# 7segement4digits1badidea-many-digits-mk-.net
KiCad netlist of a schematic drawn in EAGLE
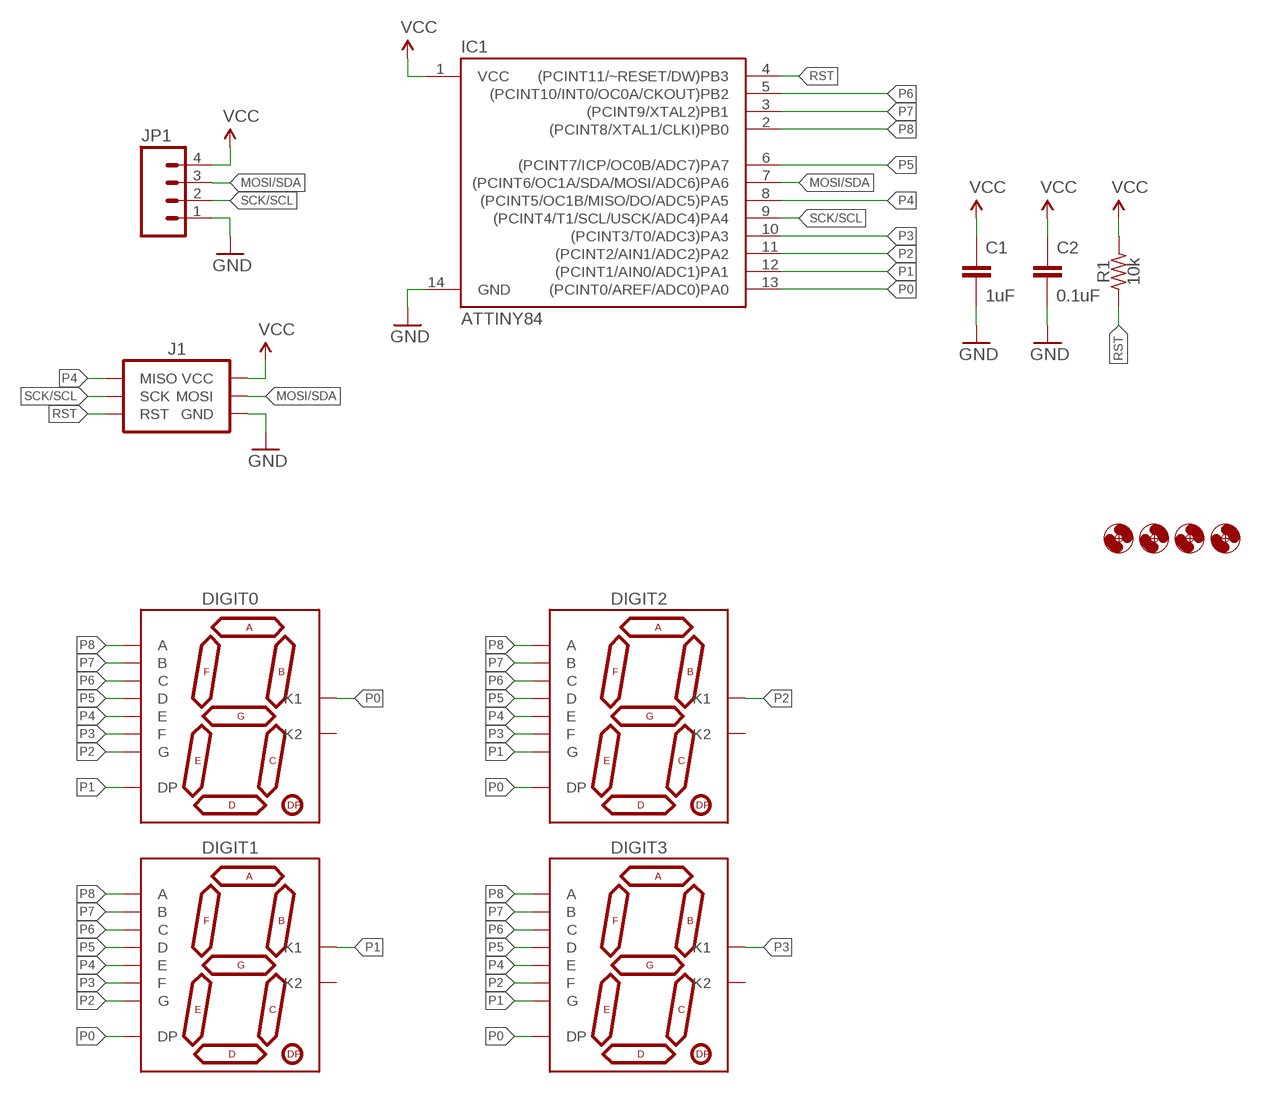
[diagram p0: schematic, sheet 1]

(export (version "E")
  (design (tool "Eeschema 10.0.6"))
  (components
    (comp (ref "C1")
      (value "1uF")
      (footprint "eagle-import:C0805")
      (libsource (lib "eagle-import") (part "CAPACITOR-CERAMICC0805"))
    )
    (comp (ref "C2")
      (value "0.1uF")
      (footprint "eagle-import:C0603")
      (libsource (lib "eagle-import") (part "CAPACITOR-CERAMICC0603"))
    )
    (comp (ref "DIGIT0")
      (value "7SEG_1DIGPTH-25.4MM")
      (footprint "eagle-import:7SEG_1DIG_25.4MM")
      (libsource (lib "eagle-import") (part "7SEG_1DIGPTH-25.4MM"))
    )
    (comp (ref "DIGIT1")
      (value "7SEG_1DIGPTH-25.4MM")
      (footprint "eagle-import:7SEG_1DIG_25.4MM")
      (libsource (lib "eagle-import") (part "7SEG_1DIGPTH-25.4MM"))
    )
    (comp (ref "DIGIT2")
      (value "7SEG_1DIGPTH-25.4MM")
      (footprint "eagle-import:7SEG_1DIG_25.4MM")
      (libsource (lib "eagle-import") (part "7SEG_1DIGPTH-25.4MM"))
    )
    (comp (ref "DIGIT3")
      (value "7SEG_1DIGPTH-25.4MM")
      (footprint "eagle-import:7SEG_1DIG_25.4MM")
      (libsource (lib "eagle-import") (part "7SEG_1DIGPTH-25.4MM"))
    )
    (comp (ref "H1")
      (value "HOLE#2")
      (footprint "eagle-import:HOLE-#2")
      (libsource (lib "eagle-import") (part "HOLE#2"))
    )
    (comp (ref "H2")
      (value "HOLE#2")
      (footprint "eagle-import:HOLE-#2")
      (libsource (lib "eagle-import") (part "HOLE#2"))
    )
    (comp (ref "H3")
      (value "HOLE#2")
      (footprint "eagle-import:HOLE-#2")
      (libsource (lib "eagle-import") (part "HOLE#2"))
    )
    (comp (ref "H4")
      (value "HOLE#2")
      (footprint "eagle-import:HOLE-#2")
      (libsource (lib "eagle-import") (part "HOLE#2"))
    )
    (comp (ref "IC1")
      (value "ATTINY84")
      (footprint "eagle-import:SO14")
      (libsource (lib "eagle-import") (part "ATTINY84"))
    )
    (comp (ref "J1")
      (value "AVR_SPI_PRG_6PTH")
      (footprint "eagle-import:2X3")
      (libsource (lib "eagle-import") (part "AVR_SPI_PRG_6PTH"))
    )
    (comp (ref "JP1")
      (value "M04PTH")
      (footprint "eagle-import:1X04-PTH-VERT")
      (libsource (lib "eagle-import") (part "M04PTH"))
    )
    (comp (ref "R1")
      (value "10k")
      (footprint "eagle-import:R0603")
      (libsource (lib "eagle-import") (part "RESISTORR0603"))
    )
  )
  (nets
    (net (code "1") (name "GND") (class "Default")
      (node (ref "C1") (pin "2") (pinfunction "2_2") (pintype "passive"))
      (node (ref "C2") (pin "2") (pinfunction "2_2") (pintype "passive"))
      (node (ref "IC1") (pin "14") (pinfunction "GND_14") (pintype "bidirectional"))
      (node (ref "J1") (pin "6") (pinfunction "GND_6") (pintype "passive"))
      (node (ref "JP1") (pin "1") (pinfunction "1_1") (pintype "passive"))
    )
    (net (code "2") (name "MOSI{slash}SDA") (class "Default")
      (node (ref "IC1") (pin "7") (pinfunction "(PCINT6/OC1A/SDA/MOSI/ADC6)PA6_7") (pintype "bidirectional"))
      (node (ref "J1") (pin "4") (pinfunction "MOSI_4") (pintype "passive"))
      (node (ref "JP1") (pin "3") (pinfunction "3_3") (pintype "passive"))
    )
    (net (code "3") (name "P0") (class "Default")
      (node (ref "DIGIT0") (pin "3") (pinfunction "K1_3") (pintype "bidirectional"))
      (node (ref "DIGIT1") (pin "5") (pinfunction "DP_5") (pintype "bidirectional"))
      (node (ref "DIGIT2") (pin "5") (pinfunction "DP_5") (pintype "bidirectional"))
      (node (ref "DIGIT3") (pin "5") (pinfunction "DP_5") (pintype "bidirectional"))
      (node (ref "IC1") (pin "13") (pinfunction "(PCINT0/AREF/ADC0)PA0_13") (pintype "bidirectional"))
    )
    (net (code "4") (name "P1") (class "Default")
      (node (ref "DIGIT0") (pin "5") (pinfunction "DP_5") (pintype "bidirectional"))
      (node (ref "DIGIT1") (pin "3") (pinfunction "K1_3") (pintype "bidirectional"))
      (node (ref "DIGIT2") (pin "10") (pinfunction "G_10") (pintype "bidirectional"))
      (node (ref "DIGIT3") (pin "10") (pinfunction "G_10") (pintype "bidirectional"))
      (node (ref "IC1") (pin "12") (pinfunction "(PCINT1/AIN0/ADC1)PA1_12") (pintype "bidirectional"))
    )
    (net (code "5") (name "P2") (class "Default")
      (node (ref "DIGIT0") (pin "10") (pinfunction "G_10") (pintype "bidirectional"))
      (node (ref "DIGIT1") (pin "10") (pinfunction "G_10") (pintype "bidirectional"))
      (node (ref "DIGIT2") (pin "3") (pinfunction "K1_3") (pintype "bidirectional"))
      (node (ref "DIGIT3") (pin "9") (pinfunction "F_9") (pintype "bidirectional"))
      (node (ref "IC1") (pin "11") (pinfunction "(PCINT2/AIN1/ADC2)PA2_11") (pintype "bidirectional"))
    )
    (net (code "6") (name "P3") (class "Default")
      (node (ref "DIGIT0") (pin "9") (pinfunction "F_9") (pintype "bidirectional"))
      (node (ref "DIGIT1") (pin "9") (pinfunction "F_9") (pintype "bidirectional"))
      (node (ref "DIGIT2") (pin "9") (pinfunction "F_9") (pintype "bidirectional"))
      (node (ref "DIGIT3") (pin "3") (pinfunction "K1_3") (pintype "bidirectional"))
      (node (ref "IC1") (pin "10") (pinfunction "(PCINT3/T0/ADC3)PA3_10") (pintype "bidirectional"))
    )
    (net (code "7") (name "P4") (class "Default")
      (node (ref "DIGIT0") (pin "1") (pinfunction "E_1") (pintype "bidirectional"))
      (node (ref "DIGIT1") (pin "1") (pinfunction "E_1") (pintype "bidirectional"))
      (node (ref "DIGIT2") (pin "1") (pinfunction "E_1") (pintype "bidirectional"))
      (node (ref "DIGIT3") (pin "1") (pinfunction "E_1") (pintype "bidirectional"))
      (node (ref "IC1") (pin "8") (pinfunction "(PCINT5/OC1B/MISO/DO/ADC5)PA5_8") (pintype "bidirectional"))
      (node (ref "J1") (pin "1") (pinfunction "MISO_1") (pintype "passive"))
    )
    (net (code "8") (name "P5") (class "Default")
      (node (ref "DIGIT0") (pin "2") (pinfunction "D_2") (pintype "bidirectional"))
      (node (ref "DIGIT1") (pin "2") (pinfunction "D_2") (pintype "bidirectional"))
      (node (ref "DIGIT2") (pin "2") (pinfunction "D_2") (pintype "bidirectional"))
      (node (ref "DIGIT3") (pin "2") (pinfunction "D_2") (pintype "bidirectional"))
      (node (ref "IC1") (pin "6") (pinfunction "(PCINT7/ICP/OC0B/ADC7)PA7_6") (pintype "bidirectional"))
    )
    (net (code "9") (name "P6") (class "Default")
      (node (ref "DIGIT0") (pin "4") (pinfunction "C_4") (pintype "bidirectional"))
      (node (ref "DIGIT1") (pin "4") (pinfunction "C_4") (pintype "bidirectional"))
      (node (ref "DIGIT2") (pin "4") (pinfunction "C_4") (pintype "bidirectional"))
      (node (ref "DIGIT3") (pin "4") (pinfunction "C_4") (pintype "bidirectional"))
      (node (ref "IC1") (pin "5") (pinfunction "(PCINT10/INT0/OC0A/CKOUT)PB2_5") (pintype "bidirectional"))
    )
    (net (code "10") (name "P7") (class "Default")
      (node (ref "DIGIT0") (pin "6") (pinfunction "B_6") (pintype "bidirectional"))
      (node (ref "DIGIT1") (pin "6") (pinfunction "B_6") (pintype "bidirectional"))
      (node (ref "DIGIT2") (pin "6") (pinfunction "B_6") (pintype "bidirectional"))
      (node (ref "DIGIT3") (pin "6") (pinfunction "B_6") (pintype "bidirectional"))
      (node (ref "IC1") (pin "3") (pinfunction "(PCINT9/XTAL2)PB1_3") (pintype "bidirectional"))
    )
    (net (code "11") (name "P8") (class "Default")
      (node (ref "DIGIT0") (pin "7") (pinfunction "A_7") (pintype "bidirectional"))
      (node (ref "DIGIT1") (pin "7") (pinfunction "A_7") (pintype "bidirectional"))
      (node (ref "DIGIT2") (pin "7") (pinfunction "A_7") (pintype "bidirectional"))
      (node (ref "DIGIT3") (pin "7") (pinfunction "A_7") (pintype "bidirectional"))
      (node (ref "IC1") (pin "2") (pinfunction "(PCINT8/XTAL1/CLKI)PB0_2") (pintype "bidirectional"))
    )
    (net (code "12") (name "RST") (class "Default")
      (node (ref "IC1") (pin "4") (pinfunction "(PCINT11/~{RESET/DW})PB3_4") (pintype "bidirectional"))
      (node (ref "J1") (pin "5") (pinfunction "RST_5") (pintype "passive"))
      (node (ref "R1") (pin "1") (pinfunction "1_1") (pintype "passive"))
    )
    (net (code "13") (name "SCK{slash}SCL") (class "Default")
      (node (ref "IC1") (pin "9") (pinfunction "(PCINT4/T1/SCL/USCK/ADC4)PA4_9") (pintype "bidirectional"))
      (node (ref "J1") (pin "3") (pinfunction "SCK_3") (pintype "passive"))
      (node (ref "JP1") (pin "2") (pinfunction "2_2") (pintype "passive"))
    )
    (net (code "14") (name "VCC") (class "Default")
      (node (ref "C1") (pin "1") (pinfunction "1_1") (pintype "passive"))
      (node (ref "C2") (pin "1") (pinfunction "1_1") (pintype "passive"))
      (node (ref "IC1") (pin "1") (pinfunction "VCC_1") (pintype "bidirectional"))
      (node (ref "J1") (pin "2") (pinfunction "VCC_2") (pintype "passive"))
      (node (ref "JP1") (pin "4") (pinfunction "4_4") (pintype "passive"))
      (node (ref "R1") (pin "2") (pinfunction "2_2") (pintype "passive"))
    )
    (net (code "15") (name "unconnected-(DIGIT0-K2-Pad8)") (class "Default")
      (node (ref "DIGIT0") (pin "8") (pinfunction "K2_8") (pintype "bidirectional"))
    )
    (net (code "16") (name "unconnected-(DIGIT1-K2-Pad8)") (class "Default")
      (node (ref "DIGIT1") (pin "8") (pinfunction "K2_8") (pintype "bidirectional"))
    )
    (net (code "17") (name "unconnected-(DIGIT2-K2-Pad8)") (class "Default")
      (node (ref "DIGIT2") (pin "8") (pinfunction "K2_8") (pintype "bidirectional"))
    )
    (net (code "18") (name "unconnected-(DIGIT3-K2-Pad8)") (class "Default")
      (node (ref "DIGIT3") (pin "8") (pinfunction "K2_8") (pintype "bidirectional"))
    )
  )
)
